# servo-pulsadores.net
KiCad netlist of a schematic drawn in EAGLE
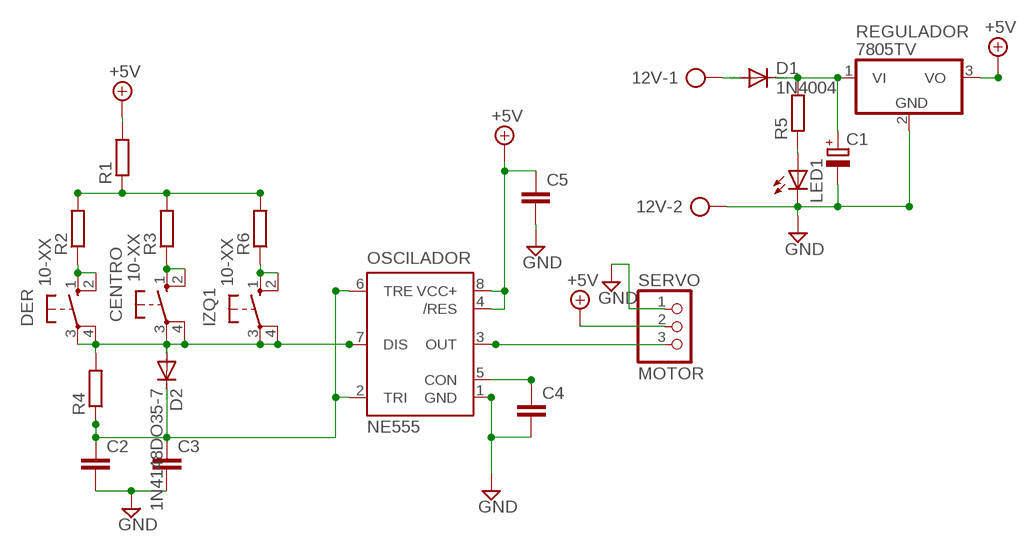
[diagram p0: schematic, sheet 1]

(export (version "E")
  (design (tool "Eeschema 10.0.6"))
  (components
    (comp (ref "12V")
      (value "AK500/2")
      (footprint "eagle-import:AK500_2")
      (libsource (lib "eagle-import") (part "AK500/2"))
    )
    (comp (ref "C1")
      (value "CPOL-EUE2.5-7")
      (footprint "eagle-import:E2,5-7")
      (libsource (lib "eagle-import") (part "CPOL-EUE2.5-7"))
    )
    (comp (ref "C2")
      (value "C-EU025-025X050")
      (footprint "eagle-import:C025-025X050")
      (libsource (lib "eagle-import") (part "C-EU025-025X050"))
    )
    (comp (ref "C3")
      (value "C-EU025-025X050")
      (footprint "eagle-import:C025-025X050")
      (libsource (lib "eagle-import") (part "C-EU025-025X050"))
    )
    (comp (ref "C4")
      (value "C-EU025-025X050")
      (footprint "eagle-import:C025-025X050")
      (libsource (lib "eagle-import") (part "C-EU025-025X050"))
    )
    (comp (ref "C5")
      (value "C-EU050-025X075")
      (footprint "eagle-import:C050-025X075")
      (libsource (lib "eagle-import") (part "C-EU050-025X075"))
    )
    (comp (ref "CENTRO")
      (value "10-XX")
      (footprint "eagle-import:B3F-10XX")
      (fields (field (name "MPN") "B3F-1000"))
      (libsource (lib "eagle-import") (part "10-XX"))
    )
    (comp (ref "D1")
      (value "1N4004")
      (footprint "eagle-import:DO41-10")
      (libsource (lib "eagle-import") (part "1N4004"))
    )
    (comp (ref "D2")
      (value "1N4148DO35-7")
      (footprint "eagle-import:DO35-7")
      (libsource (lib "eagle-import") (part "1N4148DO35-7"))
    )
    (comp (ref "DER")
      (value "10-XX")
      (footprint "eagle-import:B3F-10XX")
      (fields (field (name "MPN") "B3F-1000"))
      (libsource (lib "eagle-import") (part "10-XX"))
    )
    (comp (ref "IZQ1")
      (value "10-XX")
      (footprint "eagle-import:B3F-10XX")
      (fields (field (name "MPN") "B3F-1000"))
      (libsource (lib "eagle-import") (part "10-XX"))
    )
    (comp (ref "LED1")
      (value "LED3MM")
      (footprint "eagle-import:LED3MM")
      (libsource (lib "eagle-import") (part "LED3MM"))
    )
    (comp (ref "OSCILADOR")
      (value "NE555")
      (footprint "eagle-import:DIL-08")
      (fields (field (name "MF") "Arrow Electronics") (field (name "MPN") "NE555N"))
      (libsource (lib "eagle-import") (part "NE555"))
    )
    (comp (ref "R1")
      (value "R-EU_0207/7")
      (footprint "eagle-import:0207_7")
      (libsource (lib "eagle-import") (part "R-EU_0207/7"))
    )
    (comp (ref "R2")
      (value "R-EU_0207/7")
      (footprint "eagle-import:0207_7")
      (libsource (lib "eagle-import") (part "R-EU_0207/7"))
    )
    (comp (ref "R3")
      (value "R-EU_0207/7")
      (footprint "eagle-import:0207_7")
      (libsource (lib "eagle-import") (part "R-EU_0207/7"))
    )
    (comp (ref "R4")
      (value "R-EU_0207/7")
      (footprint "eagle-import:0207_7")
      (libsource (lib "eagle-import") (part "R-EU_0207/7"))
    )
    (comp (ref "R5")
      (value "R-EU_0207/7")
      (footprint "eagle-import:0207_7")
      (libsource (lib "eagle-import") (part "R-EU_0207/7"))
    )
    (comp (ref "R6")
      (value "R-EU_0207/7")
      (footprint "eagle-import:0207_7")
      (libsource (lib "eagle-import") (part "R-EU_0207/7"))
    )
    (comp (ref "REGULADOR")
      (value "7805TV")
      (footprint "eagle-import:TO220V")
      (libsource (lib "eagle-import") (part "78TV05"))
    )
    (comp (ref "SERVO")
      (value "MOTOR")
      (footprint "eagle-import:1X03")
      (libsource (lib "eagle-import") (part "PINHD-1X3"))
    )
  )
  (nets
    (net (code "1") (name "+5V") (class "Default")
      (node (ref "C5") (pin "1") (pinfunction "1_1") (pintype "passive"))
      (node (ref "OSCILADOR") (pin "4") (pinfunction "/RES_4") (pintype "input"))
      (node (ref "OSCILADOR") (pin "8") (pinfunction "VCC+_8") (pintype "power_in"))
      (node (ref "R1") (pin "2") (pinfunction "2_2") (pintype "passive"))
      (node (ref "REGULADOR") (pin "3") (pinfunction "VO_3") (pintype "passive"))
      (node (ref "SERVO") (pin "2") (pinfunction "2_2") (pintype "passive"))
    )
    (net (code "2") (name "GND") (class "Default")
      (node (ref "12V") (pin "2") (pinfunction "KL_2") (pintype "passive"))
      (node (ref "C1") (pin "-") (pinfunction "-_-") (pintype "passive"))
      (node (ref "C2") (pin "2") (pinfunction "2_2") (pintype "passive"))
      (node (ref "C3") (pin "2") (pinfunction "2_2") (pintype "passive"))
      (node (ref "C4") (pin "2") (pinfunction "2_2") (pintype "passive"))
      (node (ref "C5") (pin "2") (pinfunction "2_2") (pintype "passive"))
      (node (ref "LED1") (pin "K") (pinfunction "C_K") (pintype "passive"))
      (node (ref "OSCILADOR") (pin "1") (pinfunction "GND_1") (pintype "power_in"))
      (node (ref "REGULADOR") (pin "2") (pinfunction "GND_2") (pintype "passive"))
      (node (ref "SERVO") (pin "1") (pinfunction "1_1") (pintype "passive"))
    )
    (net (code "3") (name "Net-(12VA-KL)") (class "Default")
      (node (ref "12V") (pin "1") (pinfunction "KL_1") (pintype "passive"))
      (node (ref "D1") (pin "A") (pinfunction "A_A") (pintype "passive"))
    )
    (net (code "4") (name "Net-(CENTRO-P)") (class "Default")
      (node (ref "CENTRO") (pin "3") (pinfunction "P_3") (pintype "passive"))
      (node (ref "CENTRO") (pin "4") (pinfunction "P1_4") (pintype "passive"))
      (node (ref "D2") (pin "A") (pinfunction "A_A") (pintype "passive"))
      (node (ref "DER") (pin "3") (pinfunction "P_3") (pintype "passive"))
      (node (ref "DER") (pin "4") (pinfunction "P1_4") (pintype "passive"))
      (node (ref "IZQ1") (pin "3") (pinfunction "P_3") (pintype "passive"))
      (node (ref "IZQ1") (pin "4") (pinfunction "P1_4") (pintype "passive"))
      (node (ref "OSCILADOR") (pin "7") (pinfunction "DIS_7") (pintype "input"))
      (node (ref "R4") (pin "2") (pinfunction "2_2") (pintype "passive"))
    )
    (net (code "5") (name "Net-(CENTRO-S)") (class "Default")
      (node (ref "CENTRO") (pin "1") (pinfunction "S_1") (pintype "passive"))
      (node (ref "CENTRO") (pin "2") (pinfunction "S1_2") (pintype "passive"))
      (node (ref "R3") (pin "1") (pinfunction "1_1") (pintype "passive"))
    )
    (net (code "6") (name "Net-(DER-S)") (class "Default")
      (node (ref "DER") (pin "1") (pinfunction "S_1") (pintype "passive"))
      (node (ref "DER") (pin "2") (pinfunction "S1_2") (pintype "passive"))
      (node (ref "R2") (pin "1") (pinfunction "1_1") (pintype "passive"))
    )
    (net (code "7") (name "Net-(IZQ1-S)") (class "Default")
      (node (ref "IZQ1") (pin "1") (pinfunction "S_1") (pintype "passive"))
      (node (ref "IZQ1") (pin "2") (pinfunction "S1_2") (pintype "passive"))
      (node (ref "R6") (pin "1") (pinfunction "1_1") (pintype "passive"))
    )
    (net (code "8") (name "Net-(LED1-PadA)") (class "Default")
      (node (ref "LED1") (pin "A") (pinfunction "A_A") (pintype "passive"))
      (node (ref "R5") (pin "1") (pinfunction "1_1") (pintype "passive"))
    )
    (net (code "9") (name "Net-(OSCILADOR-CON)") (class "Default")
      (node (ref "C4") (pin "1") (pinfunction "1_1") (pintype "passive"))
      (node (ref "OSCILADOR") (pin "5") (pinfunction "CON_5") (pintype "input"))
    )
    (net (code "10") (name "Net-(OSCILADOR-OUT)") (class "Default")
      (node (ref "OSCILADOR") (pin "3") (pinfunction "OUT_3") (pintype "output"))
      (node (ref "SERVO") (pin "3") (pinfunction "3_3") (pintype "passive"))
    )
    (net (code "11") (name "Net-(OSCILADOR-TRE)") (class "Default")
      (node (ref "C2") (pin "1") (pinfunction "1_1") (pintype "passive"))
      (node (ref "C3") (pin "1") (pinfunction "1_1") (pintype "passive"))
      (node (ref "D2") (pin "C") (pinfunction "C_C") (pintype "passive"))
      (node (ref "OSCILADOR") (pin "2") (pinfunction "TRI_2") (pintype "input"))
      (node (ref "OSCILADOR") (pin "6") (pinfunction "TRE_6") (pintype "input"))
      (node (ref "R4") (pin "1") (pinfunction "1_1") (pintype "passive"))
    )
    (net (code "12") (name "Net-(R1-Pad1)") (class "Default")
      (node (ref "R1") (pin "1") (pinfunction "1_1") (pintype "passive"))
      (node (ref "R2") (pin "2") (pinfunction "2_2") (pintype "passive"))
      (node (ref "R3") (pin "2") (pinfunction "2_2") (pintype "passive"))
      (node (ref "R6") (pin "2") (pinfunction "2_2") (pintype "passive"))
    )
    (net (code "13") (name "Net-(REGULADOR-VI)") (class "Default")
      (node (ref "C1") (pin "+") (pinfunction "+_+") (pintype "passive"))
      (node (ref "D1") (pin "C") (pinfunction "C_C") (pintype "passive"))
      (node (ref "R5") (pin "2") (pinfunction "2_2") (pintype "passive"))
      (node (ref "REGULADOR") (pin "1") (pinfunction "VI_1") (pintype "input"))
    )
  )
)
